# Servo.net
KiCad netlist of a schematic drawn in Altium Designer
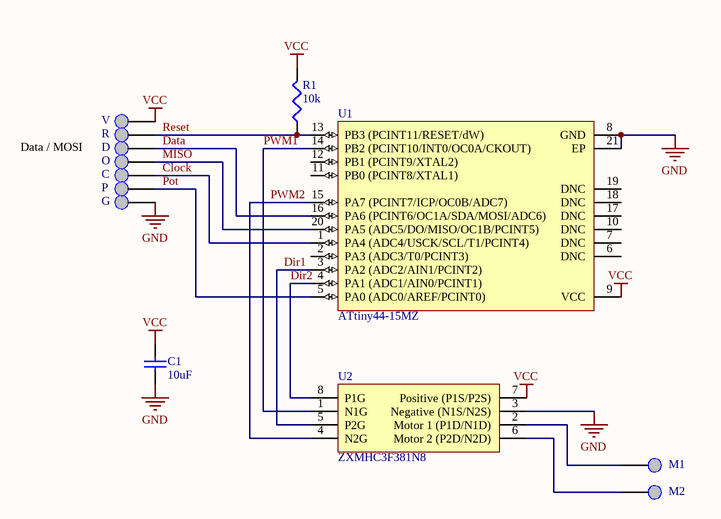
[diagram p0: Servo.SchDoc]

(export (version "E")
  (design (tool "Eeschema 10.0.6"))
  (components
    (comp (ref "C")
      (value "Test Point")
      (footprint "TestPoint")
      (libsource (lib "Thiago") (part "Test Point"))
    )
    (comp (ref "C1")
      (value "10uF")
      (footprint "0805")
      (description "Capacitor")
      (fields (field (name "Comment") "CapSMD"))
      (libsource (lib "Thiago") (part "CapSMD"))
    )
    (comp (ref "D")
      (value "Test Point")
      (footprint "TestPoint")
      (libsource (lib "Thiago") (part "Test Point"))
    )
    (comp (ref "G")
      (value "Test Point")
      (footprint "TestPoint")
      (libsource (lib "Thiago") (part "Test Point"))
    )
    (comp (ref "M1")
      (value "Test Point")
      (footprint "TestPoint")
      (libsource (lib "Thiago") (part "Test Point"))
    )
    (comp (ref "M2")
      (value "Test Point")
      (footprint "TestPoint")
      (libsource (lib "Thiago") (part "Test Point"))
    )
    (comp (ref "O")
      (value "Test Point")
      (footprint "TestPoint")
      (libsource (lib "Thiago") (part "Test Point"))
    )
    (comp (ref "P")
      (value "Test Point")
      (footprint "TestPoint")
      (libsource (lib "Thiago") (part "Test Point"))
    )
    (comp (ref "R")
      (value "Test Point")
      (footprint "TestPoint")
      (libsource (lib "Thiago") (part "Test Point"))
    )
    (comp (ref "R1")
      (value "10k")
      (footprint "RESC1608L")
      (description "Resistor")
      (fields (field (name "Comment") "ResSMD"))
      (libsource (lib "Thiago") (part "ResSMD"))
    )
    (comp (ref "U1")
      (value "ATtiny44-15MZ")
      (footprint "20M1_N")
      (fields (field (name "PUBLISHER") "Altium Limited"))
      (libsource (lib "Atmel Microcontroller 8-Bit Automotive AVR") (part "ATtiny44-15MZ"))
    )
    (comp (ref "U2")
      (value "ZXMHC3F381N8")
      (footprint "SOIC8_N")
      (description "Power Driver ICs MOSFET H-BRIDGE SOP-8L")
      (fields
        (field (name "MANUFACTURER") "Diodes Inc. / Zetex")
        (field (name "MANUFACTURER PART NUMBER") "ZXMHC3F381N8TC")
      )
      (libsource (lib "Thiago") (part "ZXMHC3F381N8TC"))
    )
    (comp (ref "V")
      (value "Test Point")
      (footprint "TestPoint")
      (libsource (lib "Thiago") (part "Test Point"))
    )
  )
  (nets
    (net (code "1") (name "/Clock") (class "Default")
      (node (ref "C") (pin "1") (pinfunction "1_1") (pintype "passive"))
      (node (ref "U1") (pin "1") (pinfunction "PA4_(ADC4/USCK/SCL/T1/PCINT4)_1") (pintype "bidirectional"))
    )
    (net (code "2") (name "/Data") (class "Default")
      (node (ref "D") (pin "1") (pinfunction "1_1") (pintype "passive"))
      (node (ref "U1") (pin "16") (pinfunction "PA6_(PCINT6/OC1A/SDA/MOSI/ADC6)_16") (pintype "bidirectional"))
    )
    (net (code "3") (name "/Dir1") (class "Default")
      (node (ref "U1") (pin "3") (pinfunction "PA2_(ADC2/AIN1/PCINT2)_3") (pintype "bidirectional"))
      (node (ref "U2") (pin "5") (pinfunction "P2G_5") (pintype "passive"))
    )
    (net (code "4") (name "/Dir2") (class "Default")
      (node (ref "U1") (pin "4") (pinfunction "PA1_(ADC1/AIN0/PCINT1)_4") (pintype "bidirectional"))
      (node (ref "U2") (pin "8") (pinfunction "P1G_8") (pintype "passive"))
    )
    (net (code "5") (name "/MISO") (class "Default")
      (node (ref "O") (pin "1") (pinfunction "1_1") (pintype "passive"))
      (node (ref "U1") (pin "20") (pinfunction "PA5_(ADC5/DO/MISO/OC1B/PCINT5)_20") (pintype "bidirectional"))
    )
    (net (code "6") (name "/PWM1") (class "Default")
      (node (ref "U1") (pin "14") (pinfunction "PB2_(PCINT10/INT0/OC0A/CKOUT)_14") (pintype "bidirectional"))
      (node (ref "U2") (pin "1") (pinfunction "N1G_1") (pintype "passive"))
    )
    (net (code "7") (name "/PWM2") (class "Default")
      (node (ref "U1") (pin "15") (pinfunction "PA7_(PCINT7/ICP/OC0B/ADC7)_15") (pintype "bidirectional"))
      (node (ref "U2") (pin "4") (pinfunction "N2G_4") (pintype "passive"))
    )
    (net (code "8") (name "/Pot") (class "Default")
      (node (ref "P") (pin "1") (pinfunction "1_1") (pintype "passive"))
      (node (ref "U1") (pin "5") (pinfunction "PA0_(ADC0/AREF/PCINT0)_5") (pintype "bidirectional"))
    )
    (net (code "9") (name "/Reset") (class "Default")
      (node (ref "R") (pin "1") (pinfunction "1_1") (pintype "passive"))
      (node (ref "R1") (pin "1") (pinfunction "1_1") (pintype "passive"))
      (node (ref "U1") (pin "13") (pinfunction "PB3_(PCINT11/RESET/dW)_13") (pintype "bidirectional"))
    )
    (net (code "10") (name "GND") (class "Default")
      (node (ref "C1") (pin "1") (pinfunction "1_1") (pintype "passive"))
      (node (ref "G") (pin "1") (pinfunction "1_1") (pintype "passive"))
      (node (ref "U1") (pin "21") (pinfunction "EP_21") (pintype "power_in"))
      (node (ref "U1") (pin "8") (pinfunction "GND_8") (pintype "power_in"))
      (node (ref "U2") (pin "3") (pinfunction "Negative_(N1S/N2S)_3") (pintype "passive"))
    )
    (net (code "11") (name "Net-(U2-Motor_1_(P1D{slash}N1D))") (class "Default")
      (node (ref "M1") (pin "1") (pinfunction "1_1") (pintype "passive"))
      (node (ref "U2") (pin "2") (pinfunction "Motor_1_(P1D/N1D)_2") (pintype "passive"))
    )
    (net (code "12") (name "Net-(U2-Motor_2_(P2D{slash}N2D))") (class "Default")
      (node (ref "M2") (pin "1") (pinfunction "1_1") (pintype "passive"))
      (node (ref "U2") (pin "6") (pinfunction "Motor_2_(P2D/N2D)_6") (pintype "passive"))
    )
    (net (code "13") (name "VCC") (class "Default")
      (node (ref "C1") (pin "2") (pinfunction "2_2") (pintype "passive"))
      (node (ref "R1") (pin "2") (pinfunction "2_2") (pintype "passive"))
      (node (ref "U1") (pin "9") (pinfunction "VCC_9") (pintype "power_in"))
      (node (ref "U2") (pin "7") (pinfunction "Positive_(P1S/P2S)_7") (pintype "passive"))
      (node (ref "V") (pin "1") (pinfunction "1_1") (pintype "passive"))
    )
    (net (code "14") (name "unconnected-(U1-DNC-Pad6)") (class "Default")
      (node (ref "U1") (pin "6") (pinfunction "DNC_6") (pintype "passive"))
    )
    (net (code "15") (name "unconnected-(U1-DNC-Pad7)") (class "Default")
      (node (ref "U1") (pin "7") (pinfunction "DNC_7") (pintype "passive"))
    )
    (net (code "16") (name "unconnected-(U1-DNC-Pad10)") (class "Default")
      (node (ref "U1") (pin "10") (pinfunction "DNC_10") (pintype "passive"))
    )
    (net (code "17") (name "unconnected-(U1-DNC-Pad17)") (class "Default")
      (node (ref "U1") (pin "17") (pinfunction "DNC_17") (pintype "passive"))
    )
    (net (code "18") (name "unconnected-(U1-DNC-Pad18)") (class "Default")
      (node (ref "U1") (pin "18") (pinfunction "DNC_18") (pintype "passive"))
    )
    (net (code "19") (name "unconnected-(U1-DNC-Pad19)") (class "Default")
      (node (ref "U1") (pin "19") (pinfunction "DNC_19") (pintype "passive"))
    )
    (net (code "20") (name "unconnected-(U1-PA3_(ADC3{slash}T0{slash}PCINT3)-Pad2)") (class "Default")
      (node (ref "U1") (pin "2") (pinfunction "PA3_(ADC3/T0/PCINT3)_2") (pintype "bidirectional"))
    )
    (net (code "21") (name "unconnected-(U1-PB0_(PCINT8{slash}XTAL1)-Pad11)") (class "Default")
      (node (ref "U1") (pin "11") (pinfunction "PB0_(PCINT8/XTAL1)_11") (pintype "bidirectional"))
    )
    (net (code "22") (name "unconnected-(U1-PB1_(PCINT9{slash}XTAL2)-Pad12)") (class "Default")
      (node (ref "U1") (pin "12") (pinfunction "PB1_(PCINT9/XTAL2)_12") (pintype "bidirectional"))
    )
  )
)
